# lab2_kozlov_buck_boost.net
KiCad netlist of a schematic drawn in Altium Designer
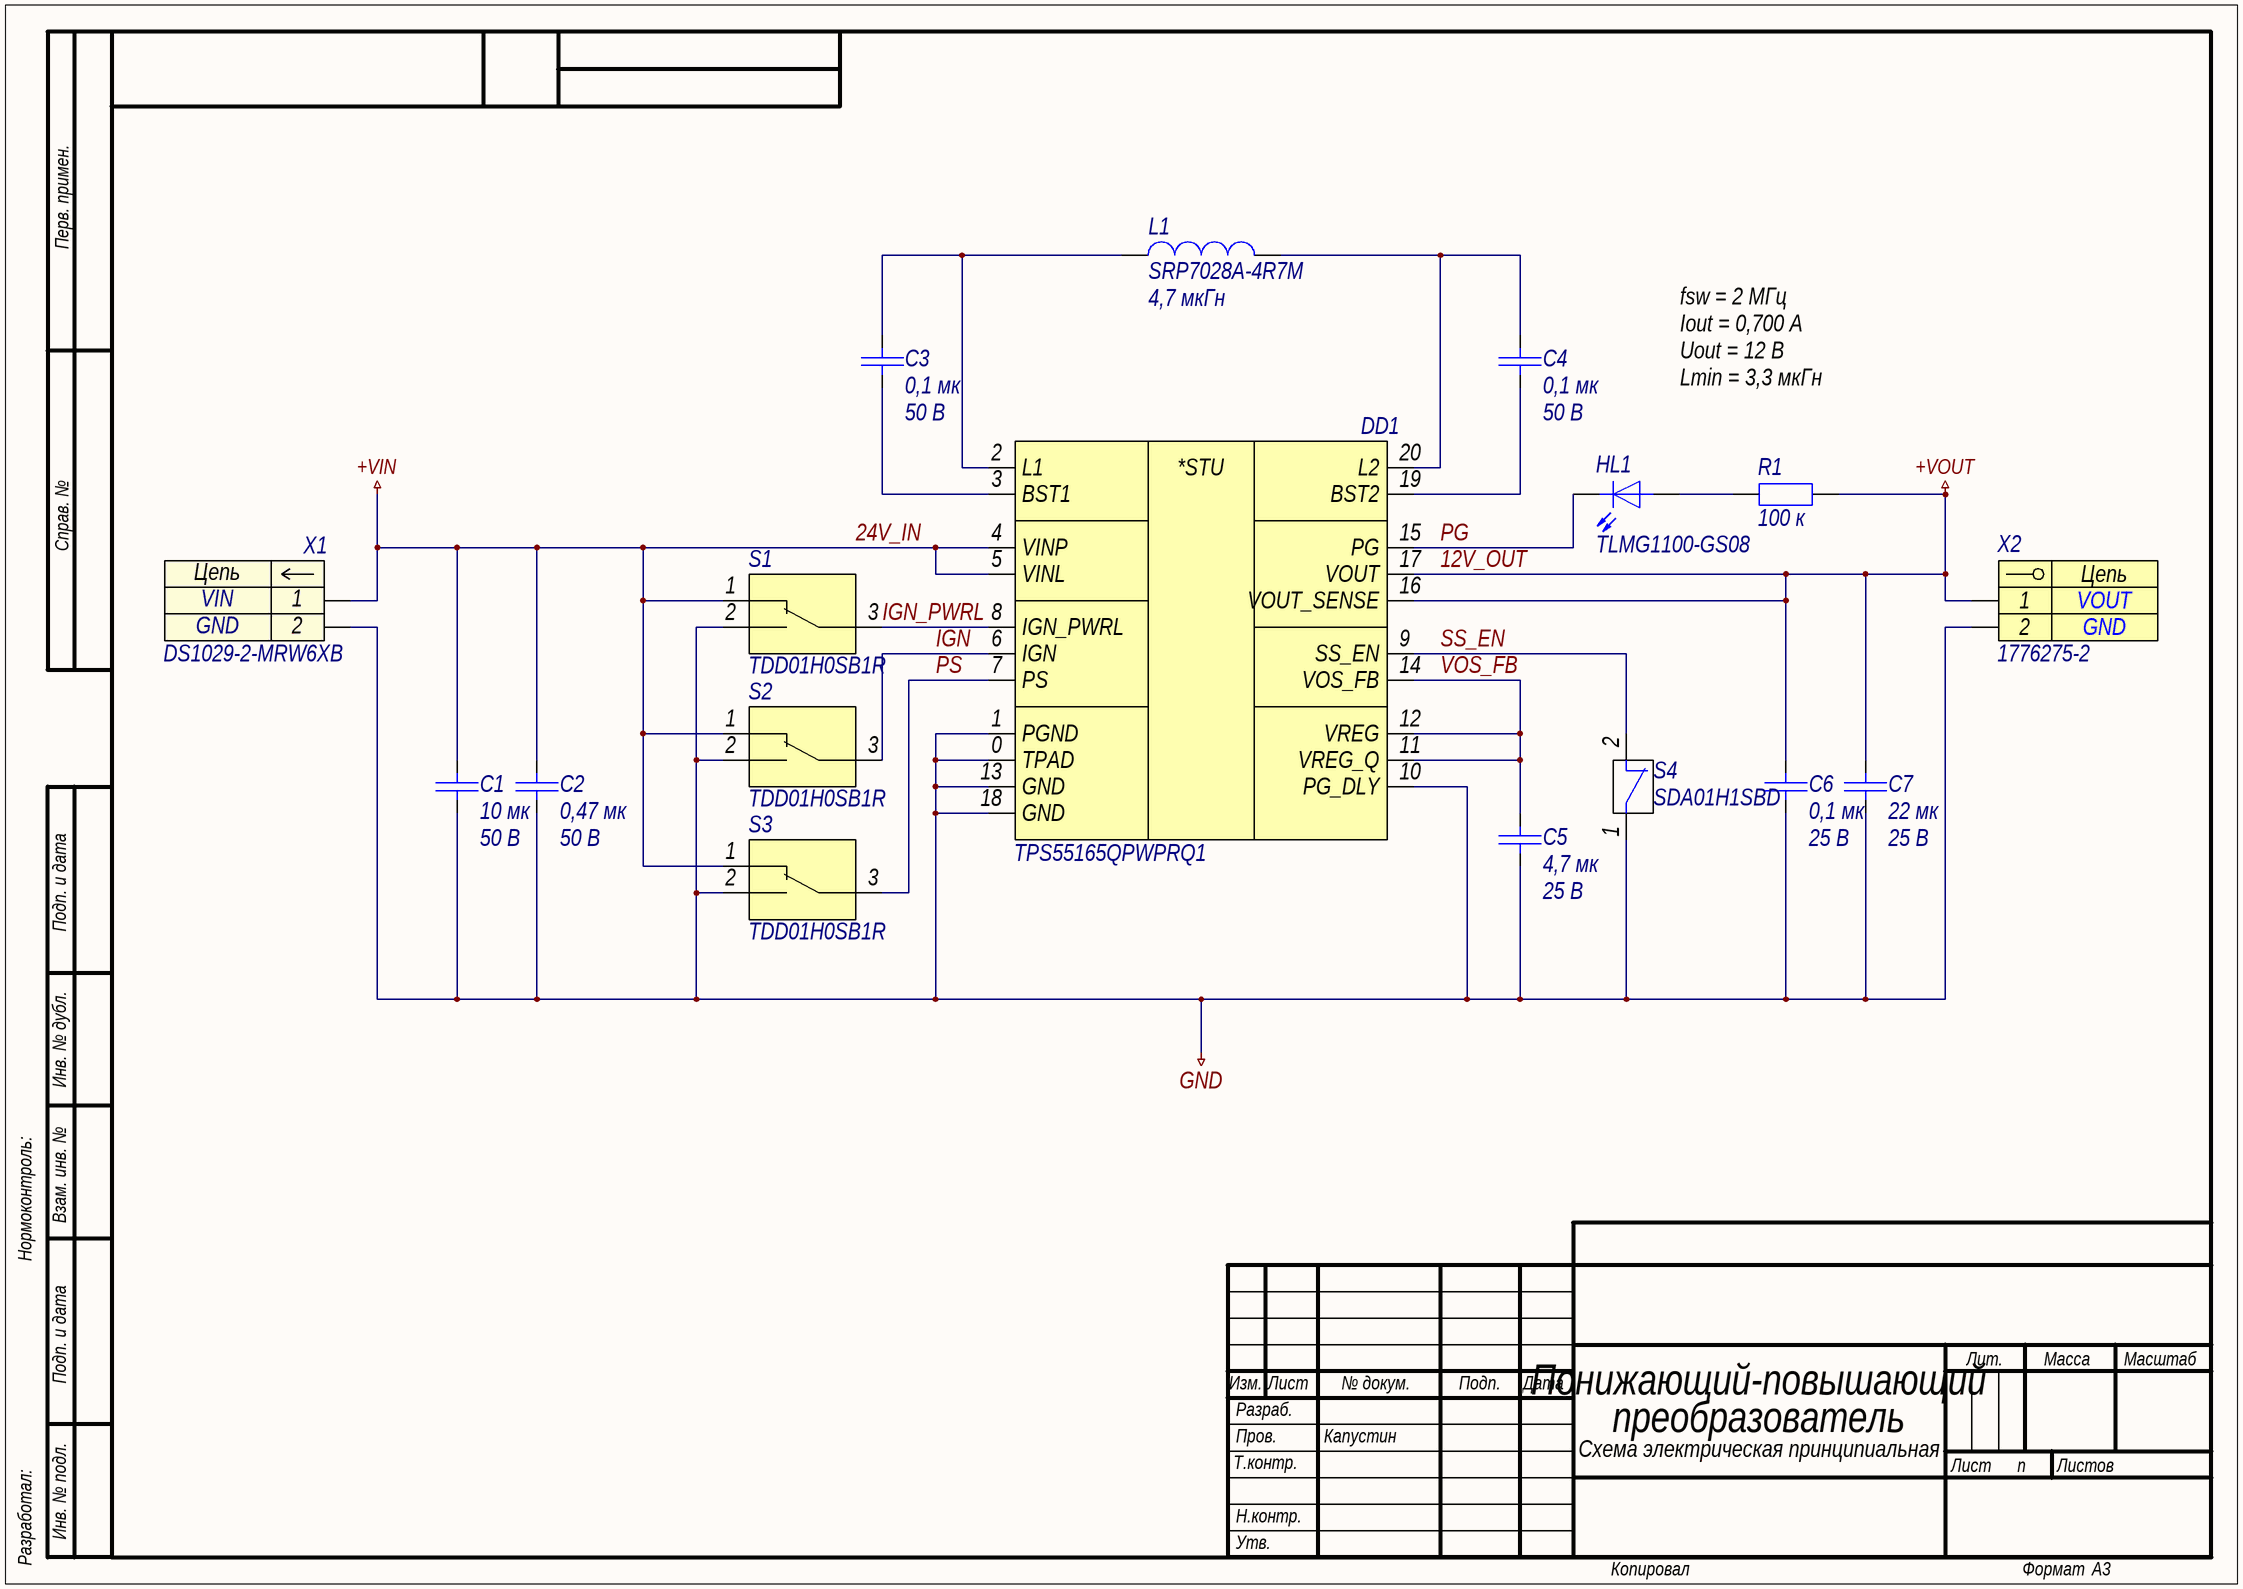
[diagram p0: lab2_kozlov_buck_boost.SchDoc]

(export (version "E")
  (design (tool "Eeschema 10.0.6"))
  (components
    (comp (ref "C1")
      (value "10 мк")
      (footprint "C0805")
      (description "=Описание")
      (fields (field (name "НАПРЯЖЕНИЕ") "50 В"))
      (libsource (lib "Database_Students") (part "C-NONPOLAR"))
    )
    (comp (ref "C2")
      (value "0,47 мк")
      (footprint "C0603")
      (description "=Описание")
      (fields (field (name "НАПРЯЖЕНИЕ") "50 В"))
      (libsource (lib "Database_Students") (part "C-NONPOLAR"))
    )
    (comp (ref "C3")
      (value "0,1 мк")
      (footprint "C0603")
      (description "=Описание")
      (fields (field (name "НАПРЯЖЕНИЕ") "50 В"))
      (libsource (lib "Database_Students") (part "C-NONPOLAR"))
    )
    (comp (ref "C4")
      (value "0,1 мк")
      (footprint "C0603")
      (description "=Описание")
      (fields (field (name "НАПРЯЖЕНИЕ") "50 В"))
      (libsource (lib "Database_Students") (part "C-NONPOLAR"))
    )
    (comp (ref "C5")
      (value "4,7 мк")
      (footprint "C0603")
      (description "=Описание")
      (fields (field (name "НАПРЯЖЕНИЕ") "25 В"))
      (libsource (lib "Database_Students") (part "C-NONPOLAR"))
    )
    (comp (ref "C6")
      (value "0,1 мк")
      (footprint "C0402")
      (description "=Описание")
      (fields (field (name "НАПРЯЖЕНИЕ") "25 В"))
      (libsource (lib "Database_Students") (part "C-NONPOLAR"))
    )
    (comp (ref "C7")
      (value "22 мк")
      (footprint "C1206")
      (description "=Описание")
      (fields (field (name "НАПРЯЖЕНИЕ") "25 В"))
      (libsource (lib "Database_Students") (part "C-NONPOLAR"))
    )
    (comp (ref "DD1")
      (value "TPS55165QPWPRQ1")
      (footprint "HTSSOP-20")
      (description "=Описание")
      (libsource (lib "Database_Students") (part "TPS55165QPWPRQ1"))
    )
    (comp (ref "HL1")
      (value "TLMG1100-GS08")
      (footprint "HL0603")
      (description "=Описание")
      (libsource (lib "Database_Students") (part "HL-COMMON"))
    )
    (comp (ref "L1")
      (value "SRP7028A-4R7M")
      (footprint "SRP-2-730X660X280")
      (description "=Описание")
      (fields (field (name "ИНДУКТИВНОСТЬ") "4,7 мкГн"))
      (libsource (lib "Database_Students") (part "INDUCTOR-COMMON"))
    )
    (comp (ref "R1")
      (value "100 к")
      (footprint "R0603")
      (description "=Описание")
      (libsource (lib "Database_Students") (part "R-COMMON"))
    )
    (comp (ref "S1")
      (value "TDD01H0SB1R")
      (footprint "TDD01H0SB1R")
      (description "=Описание")
      (libsource (lib "Database_Students") (part "SWITCH-3C"))
    )
    (comp (ref "S2")
      (value "TDD01H0SB1R")
      (footprint "TDD01H0SB1R")
      (description "=Описание")
      (libsource (lib "Database_Students") (part "SWITCH-3C"))
    )
    (comp (ref "S3")
      (value "TDD01H0SB1R")
      (footprint "TDD01H0SB1R")
      (description "=Описание")
      (libsource (lib "Database_Students") (part "SWITCH-3C"))
    )
    (comp (ref "S4")
      (value "SDA01H1SBD")
      (footprint "SDA01H1SBD")
      (description "=Описание")
      (libsource (lib "Database_Students") (part "SWITCH-2C"))
    )
    (comp (ref "X1")
      (value "DS1029-2-MRW6XB")
      (footprint "DS1029-2-MRW6XB")
      (description "=Описание")
      (libsource (lib "Database_Students") (part "HEADER-2-PLG"))
    )
    (comp (ref "X2")
      (value "1776275-2")
      (footprint "1776275-2")
      (description "=Описание")
      (libsource (lib "Database_Students") (part "HEADER-2-TRM"))
    )
  )
  (nets
    (net (code "1") (name "+VIN") (class "Default")
      (node (ref "C1") (pin "1") (pinfunction "1_1") (pintype "passive"))
      (node (ref "C2") (pin "1") (pinfunction "1_1") (pintype "passive"))
      (node (ref "DD1") (pin "4") (pinfunction "VINP_4") (pintype "passive"))
      (node (ref "DD1") (pin "5") (pinfunction "VINL_5") (pintype "passive"))
      (node (ref "S1") (pin "1") (pinfunction "1_1") (pintype "passive"))
      (node (ref "S2") (pin "1") (pinfunction "1_1") (pintype "passive"))
      (node (ref "S3") (pin "1") (pinfunction "1_1") (pintype "passive"))
      (node (ref "X1") (pin "1") (pinfunction "1_1") (pintype "passive"))
    )
    (net (code "2") (name "+VOUT") (class "Default")
      (node (ref "C6") (pin "1") (pinfunction "1_1") (pintype "passive"))
      (node (ref "C7") (pin "1") (pinfunction "1_1") (pintype "passive"))
      (node (ref "DD1") (pin "16") (pinfunction "VOUT_SENSE_16") (pintype "passive"))
      (node (ref "DD1") (pin "17") (pinfunction "VOUT_17") (pintype "passive"))
      (node (ref "R1") (pin "2") (pinfunction "2_2") (pintype "passive"))
      (node (ref "X2") (pin "1") (pinfunction "1_1") (pintype "passive"))
    )
    (net (code "3") (name "/IGN") (class "Default")
      (node (ref "DD1") (pin "6") (pinfunction "IGN_6") (pintype "passive"))
      (node (ref "S2") (pin "3") (pinfunction "3_3") (pintype "passive"))
    )
    (net (code "4") (name "/IGN_PWRL") (class "Default")
      (node (ref "DD1") (pin "8") (pinfunction "IGN_PWRL_8") (pintype "passive"))
      (node (ref "S1") (pin "3") (pinfunction "3_3") (pintype "passive"))
    )
    (net (code "5") (name "/PG") (class "Default")
      (node (ref "DD1") (pin "15") (pinfunction "PG_15") (pintype "passive"))
      (node (ref "HL1") (pin "1") (pinfunction "1_1") (pintype "passive"))
    )
    (net (code "6") (name "/PS") (class "Default")
      (node (ref "DD1") (pin "7") (pinfunction "PS_7") (pintype "passive"))
      (node (ref "S3") (pin "3") (pinfunction "3_3") (pintype "passive"))
    )
    (net (code "7") (name "/SS_EN") (class "Default")
      (node (ref "DD1") (pin "9") (pinfunction "SS_EN_9") (pintype "passive"))
      (node (ref "S4") (pin "2") (pinfunction "2_2") (pintype "passive"))
    )
    (net (code "8") (name "/VOS_FB") (class "Default")
      (node (ref "C5") (pin "1") (pinfunction "1_1") (pintype "passive"))
      (node (ref "DD1") (pin "11") (pinfunction "VREG_Q_11") (pintype "passive"))
      (node (ref "DD1") (pin "12") (pinfunction "VREG_12") (pintype "passive"))
      (node (ref "DD1") (pin "14") (pinfunction "VOS_FB_14") (pintype "passive"))
    )
    (net (code "9") (name "GND") (class "Default")
      (node (ref "C1") (pin "2") (pinfunction "2_2") (pintype "passive"))
      (node (ref "C2") (pin "2") (pinfunction "2_2") (pintype "passive"))
      (node (ref "C5") (pin "2") (pinfunction "2_2") (pintype "passive"))
      (node (ref "C6") (pin "2") (pinfunction "2_2") (pintype "passive"))
      (node (ref "C7") (pin "2") (pinfunction "2_2") (pintype "passive"))
      (node (ref "DD1") (pin "0") (pinfunction "TPAD_0") (pintype "passive"))
      (node (ref "DD1") (pin "1") (pinfunction "PGND_1") (pintype "passive"))
      (node (ref "DD1") (pin "10") (pinfunction "PG_DLY_10") (pintype "passive"))
      (node (ref "DD1") (pin "13") (pinfunction "GND_13") (pintype "passive"))
      (node (ref "DD1") (pin "18") (pinfunction "GND_18") (pintype "passive"))
      (node (ref "S1") (pin "2") (pinfunction "2_2") (pintype "passive"))
      (node (ref "S2") (pin "2") (pinfunction "2_2") (pintype "passive"))
      (node (ref "S3") (pin "2") (pinfunction "2_2") (pintype "passive"))
      (node (ref "S4") (pin "1") (pinfunction "1_1") (pintype "passive"))
      (node (ref "X1") (pin "2") (pinfunction "2_2") (pintype "passive"))
      (node (ref "X2") (pin "2") (pinfunction "2_2") (pintype "passive"))
    )
    (net (code "10") (name "Net-(DD1-BST1)") (class "Default")
      (node (ref "C3") (pin "2") (pinfunction "2_2") (pintype "passive"))
      (node (ref "DD1") (pin "3") (pinfunction "BST1_3") (pintype "passive"))
    )
    (net (code "11") (name "Net-(DD1-BST2)") (class "Default")
      (node (ref "C4") (pin "2") (pinfunction "2_2") (pintype "passive"))
      (node (ref "DD1") (pin "19") (pinfunction "BST2_19") (pintype "passive"))
    )
    (net (code "12") (name "Net-(DD1-L1)") (class "Default")
      (node (ref "C3") (pin "1") (pinfunction "1_1") (pintype "passive"))
      (node (ref "DD1") (pin "2") (pinfunction "L1_2") (pintype "passive"))
      (node (ref "L1") (pin "1") (pinfunction "1_1") (pintype "passive"))
    )
    (net (code "13") (name "Net-(DD1-L2)") (class "Default")
      (node (ref "C4") (pin "1") (pinfunction "1_1") (pintype "passive"))
      (node (ref "DD1") (pin "20") (pinfunction "L2_20") (pintype "passive"))
      (node (ref "L1") (pin "2") (pinfunction "2_2") (pintype "passive"))
    )
    (net (code "14") (name "Net-(HL1-Pad2)") (class "Default")
      (node (ref "HL1") (pin "2") (pinfunction "2_2") (pintype "passive"))
      (node (ref "R1") (pin "1") (pinfunction "1_1") (pintype "passive"))
    )
  )
)
